# P09_DDRA_B_NOVTT.net
KiCad netlist of a schematic drawn in Altium Designer
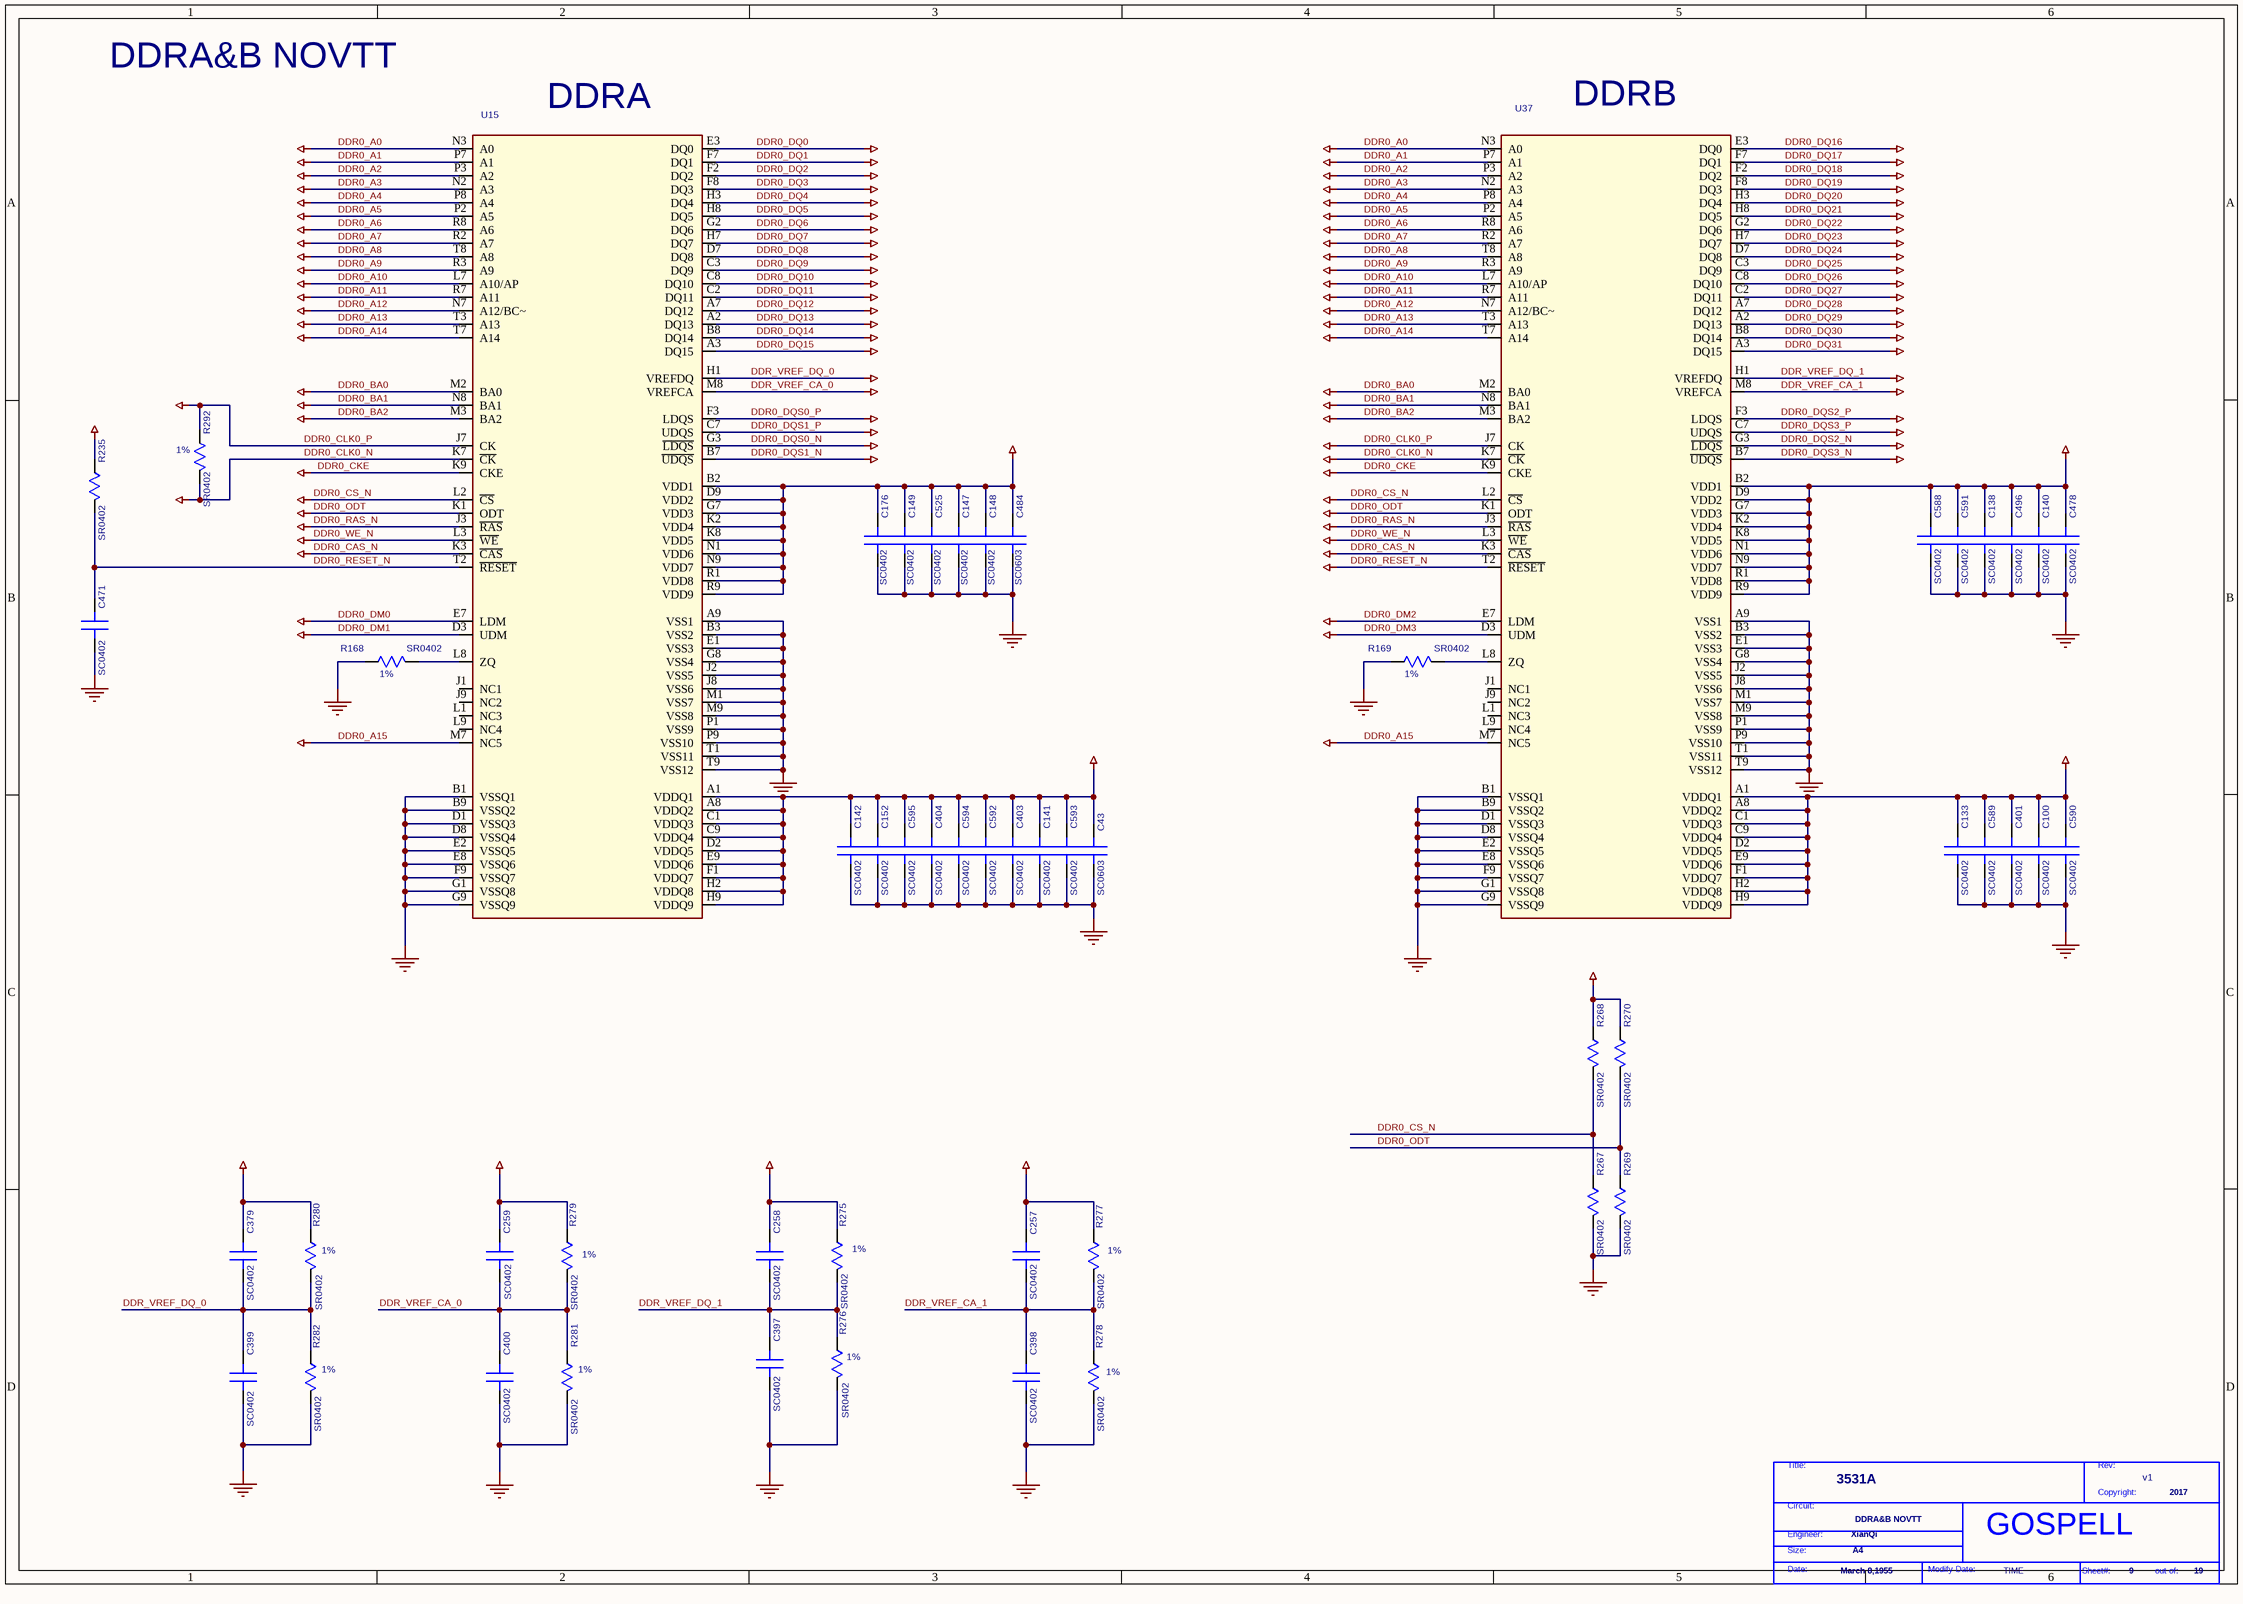
[diagram p0: P09 DDRA&B NOVTT.SchDoc]

(export (version "E")
  (design (tool "Eeschema 10.0.6"))
  (components
    (comp (ref "C43") (value "SC0603") (libsource (lib "*") (part "C_0_Dup2")))
    (comp (ref "C100") (value "SC0402") (libsource (lib "*") (part "C_0_Dup2")))
    (comp (ref "C133") (value "SC0402") (libsource (lib "*") (part "C_0_Dup2")))
    (comp (ref "C138") (value "SC0402") (libsource (lib "*") (part "C_0_Dup2")))
    (comp (ref "C140") (value "SC0402") (libsource (lib "*") (part "C_0_Dup2")))
    (comp (ref "C141") (value "SC0402") (libsource (lib "*") (part "C_0_Dup2")))
    (comp (ref "C142") (value "SC0402") (libsource (lib "*") (part "C_0_Dup2")))
    (comp (ref "C147") (value "SC0402") (libsource (lib "*") (part "C_0_Dup2")))
    (comp (ref "C148") (value "SC0402") (libsource (lib "*") (part "C_0_Dup2")))
    (comp (ref "C149") (value "SC0402") (libsource (lib "*") (part "C_0_Dup2")))
    (comp (ref "C152") (value "SC0402") (libsource (lib "*") (part "C_0_Dup2")))
    (comp (ref "C176") (value "SC0402") (libsource (lib "*") (part "C_0_Dup2")))
    (comp (ref "C257") (value "SC0402") (libsource (lib "*") (part "C_0_Dup2")))
    (comp (ref "C258") (value "SC0402") (libsource (lib "*") (part "C_0_Dup2")))
    (comp (ref "C259") (value "SC0402") (libsource (lib "*") (part "C_0_Dup2")))
    (comp (ref "C379") (value "SC0402") (libsource (lib "*") (part "C_0_Dup2")))
    (comp (ref "C397") (value "SC0402") (libsource (lib "*") (part "C_0_Dup2")))
    (comp (ref "C398") (value "SC0402") (libsource (lib "*") (part "C_0_Dup2")))
    (comp (ref "C399") (value "SC0402") (libsource (lib "*") (part "C_0_Dup2")))
    (comp (ref "C400") (value "SC0402") (libsource (lib "*") (part "C_0_Dup2")))
    (comp (ref "C401") (value "SC0402") (libsource (lib "*") (part "C_0_Dup2")))
    (comp (ref "C403") (value "SC0402") (libsource (lib "*") (part "C_0_Dup2")))
    (comp (ref "C404") (value "SC0402") (libsource (lib "*") (part "C_0_Dup2")))
    (comp (ref "C471") (value "SC0402") (libsource (lib "*") (part "C_0_Dup2")))
    (comp (ref "C478") (value "SC0402") (libsource (lib "*") (part "C_0_Dup2")))
    (comp (ref "C484") (value "SC0603") (libsource (lib "*") (part "C_0_Dup2")))
    (comp (ref "C496") (value "SC0402") (libsource (lib "*") (part "C_0_Dup2")))
    (comp (ref "C525") (value "SC0402") (libsource (lib "*") (part "C_0_Dup2")))
    (comp (ref "C588") (value "SC0402") (libsource (lib "*") (part "C_0_Dup2")))
    (comp (ref "C589") (value "SC0402") (libsource (lib "*") (part "C_0_Dup2")))
    (comp (ref "C590") (value "SC0402") (libsource (lib "*") (part "C_0_Dup2")))
    (comp (ref "C591") (value "SC0402") (libsource (lib "*") (part "C_0_Dup2")))
    (comp (ref "C592") (value "SC0402") (libsource (lib "*") (part "C_0_Dup2")))
    (comp (ref "C593") (value "SC0402") (libsource (lib "*") (part "C_0_Dup2")))
    (comp (ref "C594") (value "SC0402") (libsource (lib "*") (part "C_0_Dup2")))
    (comp (ref "C595") (value "SC0402") (libsource (lib "*") (part "C_0_Dup2")))
    (comp (ref "R168") (value "SR0402") (libsource (lib "*") (part "R_1")))
    (comp (ref "R169") (value "SR0402") (libsource (lib "*") (part "R_1")))
    (comp (ref "R235") (value "SR0402") (libsource (lib "*") (part "R_1")))
    (comp (ref "R267") (value "SR0402") (libsource (lib "*") (part "R_1")))
    (comp (ref "R268") (value "SR0402") (libsource (lib "*") (part "R_1")))
    (comp (ref "R269") (value "SR0402") (libsource (lib "*") (part "R_1")))
    (comp (ref "R270") (value "SR0402") (libsource (lib "*") (part "R_1")))
    (comp (ref "R275") (value "SR0402") (libsource (lib "*") (part "R_1")))
    (comp (ref "R276") (value "SR0402") (libsource (lib "*") (part "R_1")))
    (comp (ref "R277") (value "SR0402") (libsource (lib "*") (part "R_1")))
    (comp (ref "R278") (value "SR0402") (libsource (lib "*") (part "R_1")))
    (comp (ref "R279") (value "SR0402") (libsource (lib "*") (part "R_1")))
    (comp (ref "R280") (value "SR0402") (libsource (lib "*") (part "R_1")))
    (comp (ref "R281") (value "SR0402") (libsource (lib "*") (part "R_1")))
    (comp (ref "R282") (value "SR0402") (libsource (lib "*") (part "R_1")))
    (comp (ref "R292") (value "SR0402") (libsource (lib "*") (part "R_1")))
    (comp (ref "U15") (value "BGA96-32-1609M") (libsource (lib "*") (part "MT41J256M16RE-15E-D_2")))
    (comp (ref "U37") (value "BGA96-32-1609M") (libsource (lib "*") (part "MT41J256M16RE-15E-D_2")))
  )
  (nets
    (net (code "1") (name "1V5") (class "Default")
      (node (ref "C100") (pin "1") (pinfunction "A_1") (pintype "passive"))
      (node (ref "C133") (pin "1") (pinfunction "A_1") (pintype "passive"))
      (node (ref "C138") (pin "1") (pinfunction "A_1") (pintype "passive"))
      (node (ref "C140") (pin "1") (pinfunction "A_1") (pintype "passive"))
      (node (ref "C141") (pin "1") (pinfunction "A_1") (pintype "passive"))
      (node (ref "C142") (pin "1") (pinfunction "A_1") (pintype "passive"))
      (node (ref "C147") (pin "1") (pinfunction "A_1") (pintype "passive"))
      (node (ref "C148") (pin "1") (pinfunction "A_1") (pintype "passive"))
      (node (ref "C149") (pin "1") (pinfunction "A_1") (pintype "passive"))
      (node (ref "C152") (pin "1") (pinfunction "A_1") (pintype "passive"))
      (node (ref "C176") (pin "1") (pinfunction "A_1") (pintype "passive"))
      (node (ref "C257") (pin "1") (pinfunction "A_1") (pintype "passive"))
      (node (ref "C258") (pin "1") (pinfunction "A_1") (pintype "passive"))
      (node (ref "C259") (pin "1") (pinfunction "A_1") (pintype "passive"))
      (node (ref "C379") (pin "1") (pinfunction "A_1") (pintype "passive"))
      (node (ref "C401") (pin "1") (pinfunction "A_1") (pintype "passive"))
      (node (ref "C403") (pin "1") (pinfunction "A_1") (pintype "passive"))
      (node (ref "C404") (pin "1") (pinfunction "A_1") (pintype "passive"))
      (node (ref "C43") (pin "1") (pinfunction "A_1") (pintype "passive"))
      (node (ref "C478") (pin "1") (pinfunction "A_1") (pintype "passive"))
      (node (ref "C484") (pin "1") (pinfunction "A_1") (pintype "passive"))
      (node (ref "C496") (pin "1") (pinfunction "A_1") (pintype "passive"))
      (node (ref "C525") (pin "1") (pinfunction "A_1") (pintype "passive"))
      (node (ref "C588") (pin "1") (pinfunction "A_1") (pintype "passive"))
      (node (ref "C589") (pin "1") (pinfunction "A_1") (pintype "passive"))
      (node (ref "C590") (pin "1") (pinfunction "A_1") (pintype "passive"))
      (node (ref "C591") (pin "1") (pinfunction "A_1") (pintype "passive"))
      (node (ref "C592") (pin "1") (pinfunction "A_1") (pintype "passive"))
      (node (ref "C593") (pin "1") (pinfunction "A_1") (pintype "passive"))
      (node (ref "C594") (pin "1") (pinfunction "A_1") (pintype "passive"))
      (node (ref "C595") (pin "1") (pinfunction "A_1") (pintype "passive"))
      (node (ref "R235") (pin "1") (pinfunction "A_1") (pintype "passive"))
      (node (ref "R268") (pin "1") (pinfunction "A_1") (pintype "passive"))
      (node (ref "R270") (pin "1") (pinfunction "A_1") (pintype "passive"))
      (node (ref "R275") (pin "1") (pinfunction "A_1") (pintype "passive"))
      (node (ref "R277") (pin "1") (pinfunction "A_1") (pintype "passive"))
      (node (ref "R279") (pin "1") (pinfunction "A_1") (pintype "passive"))
      (node (ref "R280") (pin "1") (pinfunction "A_1") (pintype "passive"))
      (node (ref "U15") (pin "A1") (pinfunction "VDDQ1_A1") (pintype "passive"))
      (node (ref "U15") (pin "A8") (pinfunction "VDDQ2_A8") (pintype "passive"))
      (node (ref "U15") (pin "B2") (pinfunction "VDD1_B2") (pintype "passive"))
      (node (ref "U15") (pin "C1") (pinfunction "VDDQ3_C1") (pintype "passive"))
      (node (ref "U15") (pin "C9") (pinfunction "VDDQ4_C9") (pintype "passive"))
      (node (ref "U15") (pin "D2") (pinfunction "VDDQ5_D2") (pintype "passive"))
      (node (ref "U15") (pin "D9") (pinfunction "VDD2_D9") (pintype "passive"))
      (node (ref "U15") (pin "E9") (pinfunction "VDDQ6_E9") (pintype "passive"))
      (node (ref "U15") (pin "F1") (pinfunction "VDDQ7_F1") (pintype "passive"))
      (node (ref "U15") (pin "G7") (pinfunction "VDD3_G7") (pintype "passive"))
      (node (ref "U15") (pin "H2") (pinfunction "VDDQ8_H2") (pintype "passive"))
      (node (ref "U15") (pin "H9") (pinfunction "VDDQ9_H9") (pintype "passive"))
      (node (ref "U15") (pin "K2") (pinfunction "VDD4_K2") (pintype "passive"))
      (node (ref "U15") (pin "K8") (pinfunction "VDD5_K8") (pintype "passive"))
      (node (ref "U15") (pin "N1") (pinfunction "VDD6_N1") (pintype "passive"))
      (node (ref "U15") (pin "N9") (pinfunction "VDD7_N9") (pintype "passive"))
      (node (ref "U15") (pin "R1") (pinfunction "VDD8_R1") (pintype "passive"))
      (node (ref "U15") (pin "R9") (pinfunction "VDD9_R9") (pintype "passive"))
      (node (ref "U37") (pin "A1") (pinfunction "VDDQ1_A1") (pintype "passive"))
      (node (ref "U37") (pin "A8") (pinfunction "VDDQ2_A8") (pintype "passive"))
      (node (ref "U37") (pin "B2") (pinfunction "VDD1_B2") (pintype "passive"))
      (node (ref "U37") (pin "C1") (pinfunction "VDDQ3_C1") (pintype "passive"))
      (node (ref "U37") (pin "C9") (pinfunction "VDDQ4_C9") (pintype "passive"))
      (node (ref "U37") (pin "D2") (pinfunction "VDDQ5_D2") (pintype "passive"))
      (node (ref "U37") (pin "D9") (pinfunction "VDD2_D9") (pintype "passive"))
      (node (ref "U37") (pin "E9") (pinfunction "VDDQ6_E9") (pintype "passive"))
      (node (ref "U37") (pin "F1") (pinfunction "VDDQ7_F1") (pintype "passive"))
      (node (ref "U37") (pin "G7") (pinfunction "VDD3_G7") (pintype "passive"))
      (node (ref "U37") (pin "H2") (pinfunction "VDDQ8_H2") (pintype "passive"))
      (node (ref "U37") (pin "H9") (pinfunction "VDDQ9_H9") (pintype "passive"))
      (node (ref "U37") (pin "K2") (pinfunction "VDD4_K2") (pintype "passive"))
      (node (ref "U37") (pin "K8") (pinfunction "VDD5_K8") (pintype "passive"))
      (node (ref "U37") (pin "N1") (pinfunction "VDD6_N1") (pintype "passive"))
      (node (ref "U37") (pin "N9") (pinfunction "VDD7_N9") (pintype "passive"))
      (node (ref "U37") (pin "R1") (pinfunction "VDD8_R1") (pintype "passive"))
      (node (ref "U37") (pin "R9") (pinfunction "VDD9_R9") (pintype "passive"))
    )
    (net (code "2") (name "DDR0_A0") (class "Default")
      (node (ref "U15") (pin "N3") (pinfunction "A0_N3") (pintype "passive"))
      (node (ref "U37") (pin "N3") (pinfunction "A0_N3") (pintype "passive"))
    )
    (net (code "3") (name "DDR0_A1") (class "Default")
      (node (ref "U15") (pin "P7") (pinfunction "A1_P7") (pintype "passive"))
      (node (ref "U37") (pin "P7") (pinfunction "A1_P7") (pintype "passive"))
    )
    (net (code "4") (name "DDR0_A2") (class "Default")
      (node (ref "U15") (pin "P3") (pinfunction "A2_P3") (pintype "passive"))
      (node (ref "U37") (pin "P3") (pinfunction "A2_P3") (pintype "passive"))
    )
    (net (code "5") (name "DDR0_A3") (class "Default")
      (node (ref "U15") (pin "N2") (pinfunction "A3_N2") (pintype "passive"))
      (node (ref "U37") (pin "N2") (pinfunction "A3_N2") (pintype "passive"))
    )
    (net (code "6") (name "DDR0_A4") (class "Default")
      (node (ref "U15") (pin "P8") (pinfunction "A4_P8") (pintype "passive"))
      (node (ref "U37") (pin "P8") (pinfunction "A4_P8") (pintype "passive"))
    )
    (net (code "7") (name "DDR0_A5") (class "Default")
      (node (ref "U15") (pin "P2") (pinfunction "A5_P2") (pintype "passive"))
      (node (ref "U37") (pin "P2") (pinfunction "A5_P2") (pintype "passive"))
    )
    (net (code "8") (name "DDR0_A6") (class "Default")
      (node (ref "U15") (pin "R8") (pinfunction "A6_R8") (pintype "passive"))
      (node (ref "U37") (pin "R8") (pinfunction "A6_R8") (pintype "passive"))
    )
    (net (code "9") (name "DDR0_A7") (class "Default")
      (node (ref "U15") (pin "R2") (pinfunction "A7_R2") (pintype "passive"))
      (node (ref "U37") (pin "R2") (pinfunction "A7_R2") (pintype "passive"))
    )
    (net (code "10") (name "DDR0_A8") (class "Default")
      (node (ref "U15") (pin "T8") (pinfunction "A8_T8") (pintype "passive"))
      (node (ref "U37") (pin "T8") (pinfunction "A8_T8") (pintype "passive"))
    )
    (net (code "11") (name "DDR0_A9") (class "Default")
      (node (ref "U15") (pin "R3") (pinfunction "A9_R3") (pintype "passive"))
      (node (ref "U37") (pin "R3") (pinfunction "A9_R3") (pintype "passive"))
    )
    (net (code "12") (name "DDR0_A10") (class "Default")
      (node (ref "U15") (pin "L7") (pinfunction "A10/AP_L7") (pintype "passive"))
      (node (ref "U37") (pin "L7") (pinfunction "A10/AP_L7") (pintype "passive"))
    )
    (net (code "13") (name "DDR0_A11") (class "Default")
      (node (ref "U15") (pin "R7") (pinfunction "A11_R7") (pintype "passive"))
      (node (ref "U37") (pin "R7") (pinfunction "A11_R7") (pintype "passive"))
    )
    (net (code "14") (name "DDR0_A12") (class "Default")
      (node (ref "U15") (pin "N7") (pinfunction "A12/BC~_N7") (pintype "passive"))
      (node (ref "U37") (pin "N7") (pinfunction "A12/BC~_N7") (pintype "passive"))
    )
    (net (code "15") (name "DDR0_A13") (class "Default")
      (node (ref "U15") (pin "T3") (pinfunction "A13_T3") (pintype "passive"))
      (node (ref "U37") (pin "T3") (pinfunction "A13_T3") (pintype "passive"))
    )
    (net (code "16") (name "DDR0_A14") (class "Default")
      (node (ref "U15") (pin "T7") (pinfunction "A14_T7") (pintype "passive"))
      (node (ref "U37") (pin "T7") (pinfunction "A14_T7") (pintype "passive"))
    )
    (net (code "17") (name "DDR0_A15") (class "Default")
      (node (ref "U15") (pin "M7") (pinfunction "NC5_M7") (pintype "passive"))
      (node (ref "U37") (pin "M7") (pinfunction "NC5_M7") (pintype "passive"))
    )
    (net (code "18") (name "DDR0_BA0") (class "Default")
      (node (ref "U15") (pin "M2") (pinfunction "BA0_M2") (pintype "passive"))
      (node (ref "U37") (pin "M2") (pinfunction "BA0_M2") (pintype "passive"))
    )
    (net (code "19") (name "DDR0_BA1") (class "Default")
      (node (ref "U15") (pin "N8") (pinfunction "BA1_N8") (pintype "passive"))
      (node (ref "U37") (pin "N8") (pinfunction "BA1_N8") (pintype "passive"))
    )
    (net (code "20") (name "DDR0_BA2") (class "Default")
      (node (ref "U15") (pin "M3") (pinfunction "BA2_M3") (pintype "passive"))
      (node (ref "U37") (pin "M3") (pinfunction "BA2_M3") (pintype "passive"))
    )
    (net (code "21") (name "DDR0_CAS_N") (class "Default")
      (node (ref "U15") (pin "K3") (pinfunction "~{CAS}_K3") (pintype "passive"))
      (node (ref "U37") (pin "K3") (pinfunction "~{CAS}_K3") (pintype "passive"))
    )
    (net (code "22") (name "DDR0_CKE") (class "Default")
      (node (ref "U15") (pin "K9") (pinfunction "CKE_K9") (pintype "passive"))
      (node (ref "U37") (pin "K9") (pinfunction "CKE_K9") (pintype "passive"))
    )
    (net (code "23") (name "DDR0_CLK0_N") (class "Default")
      (node (ref "R292") (pin "2") (pinfunction "B_2") (pintype "passive"))
      (node (ref "U15") (pin "K7") (pinfunction "~{CK}_K7") (pintype "passive"))
      (node (ref "U37") (pin "K7") (pinfunction "~{CK}_K7") (pintype "passive"))
    )
    (net (code "24") (name "DDR0_CLK0_P") (class "Default")
      (node (ref "R292") (pin "1") (pinfunction "A_1") (pintype "passive"))
      (node (ref "U15") (pin "J7") (pinfunction "CK_J7") (pintype "passive"))
      (node (ref "U37") (pin "J7") (pinfunction "CK_J7") (pintype "passive"))
    )
    (net (code "25") (name "DDR0_CS_N") (class "Default")
      (node (ref "R267") (pin "1") (pinfunction "A_1") (pintype "passive"))
      (node (ref "R268") (pin "2") (pinfunction "B_2") (pintype "passive"))
      (node (ref "U15") (pin "L2") (pinfunction "~{CS}_L2") (pintype "passive"))
      (node (ref "U37") (pin "L2") (pinfunction "~{CS}_L2") (pintype "passive"))
    )
    (net (code "26") (name "DDR0_DM0") (class "Default")
      (node (ref "U15") (pin "E7") (pinfunction "LDM_E7") (pintype "passive"))
    )
    (net (code "27") (name "DDR0_DM1") (class "Default")
      (node (ref "U15") (pin "D3") (pinfunction "UDM_D3") (pintype "passive"))
    )
    (net (code "28") (name "DDR0_DM2") (class "Default")
      (node (ref "U37") (pin "E7") (pinfunction "LDM_E7") (pintype "passive"))
    )
    (net (code "29") (name "DDR0_DM3") (class "Default")
      (node (ref "U37") (pin "D3") (pinfunction "UDM_D3") (pintype "passive"))
    )
    (net (code "30") (name "DDR0_DQ0") (class "Default")
      (node (ref "U15") (pin "E3") (pinfunction "DQ0_E3") (pintype "passive"))
    )
    (net (code "31") (name "DDR0_DQ1") (class "Default")
      (node (ref "U15") (pin "F7") (pinfunction "DQ1_F7") (pintype "passive"))
    )
    (net (code "32") (name "DDR0_DQ2") (class "Default")
      (node (ref "U15") (pin "F2") (pinfunction "DQ2_F2") (pintype "passive"))
    )
    (net (code "33") (name "DDR0_DQ3") (class "Default")
      (node (ref "U15") (pin "F8") (pinfunction "DQ3_F8") (pintype "passive"))
    )
    (net (code "34") (name "DDR0_DQ4") (class "Default")
      (node (ref "U15") (pin "H3") (pinfunction "DQ4_H3") (pintype "passive"))
    )
    (net (code "35") (name "DDR0_DQ5") (class "Default")
      (node (ref "U15") (pin "H8") (pinfunction "DQ5_H8") (pintype "passive"))
    )
    (net (code "36") (name "DDR0_DQ6") (class "Default")
      (node (ref "U15") (pin "G2") (pinfunction "DQ6_G2") (pintype "passive"))
    )
    (net (code "37") (name "DDR0_DQ7") (class "Default")
      (node (ref "U15") (pin "H7") (pinfunction "DQ7_H7") (pintype "passive"))
    )
    (net (code "38") (name "DDR0_DQ8") (class "Default")
      (node (ref "U15") (pin "D7") (pinfunction "DQ8_D7") (pintype "passive"))
    )
    (net (code "39") (name "DDR0_DQ9") (class "Default")
      (node (ref "U15") (pin "C3") (pinfunction "DQ9_C3") (pintype "passive"))
    )
    (net (code "40") (name "DDR0_DQ10") (class "Default")
      (node (ref "U15") (pin "C8") (pinfunction "DQ10_C8") (pintype "passive"))
    )
    (net (code "41") (name "DDR0_DQ11") (class "Default")
      (node (ref "U15") (pin "C2") (pinfunction "DQ11_C2") (pintype "passive"))
    )
    (net (code "42") (name "DDR0_DQ12") (class "Default")
      (node (ref "U15") (pin "A7") (pinfunction "DQ12_A7") (pintype "passive"))
    )
    (net (code "43") (name "DDR0_DQ13") (class "Default")
      (node (ref "U15") (pin "A2") (pinfunction "DQ13_A2") (pintype "passive"))
    )
    (net (code "44") (name "DDR0_DQ14") (class "Default")
      (node (ref "U15") (pin "B8") (pinfunction "DQ14_B8") (pintype "passive"))
    )
    (net (code "45") (name "DDR0_DQ15") (class "Default")
      (node (ref "U15") (pin "A3") (pinfunction "DQ15_A3") (pintype "passive"))
    )
    (net (code "46") (name "DDR0_DQ16") (class "Default")
      (node (ref "U37") (pin "E3") (pinfunction "DQ0_E3") (pintype "passive"))
    )
    (net (code "47") (name "DDR0_DQ17") (class "Default")
      (node (ref "U37") (pin "F7") (pinfunction "DQ1_F7") (pintype "passive"))
    )
    (net (code "48") (name "DDR0_DQ18") (class "Default")
      (node (ref "U37") (pin "F2") (pinfunction "DQ2_F2") (pintype "passive"))
    )
    (net (code "49") (name "DDR0_DQ19") (class "Default")
      (node (ref "U37") (pin "F8") (pinfunction "DQ3_F8") (pintype "passive"))
    )
    (net (code "50") (name "DDR0_DQ20") (class "Default")
      (node (ref "U37") (pin "H3") (pinfunction "DQ4_H3") (pintype "passive"))
    )
    (net (code "51") (name "DDR0_DQ21") (class "Default")
      (node (ref "U37") (pin "H8") (pinfunction "DQ5_H8") (pintype "passive"))
    )
    (net (code "52") (name "DDR0_DQ22") (class "Default")
      (node (ref "U37") (pin "G2") (pinfunction "DQ6_G2") (pintype "passive"))
    )
    (net (code "53") (name "DDR0_DQ23") (class "Default")
      (node (ref "U37") (pin "H7") (pinfunction "DQ7_H7") (pintype "passive"))
    )
    (net (code "54") (name "DDR0_DQ24") (class "Default")
      (node (ref "U37") (pin "D7") (pinfunction "DQ8_D7") (pintype "passive"))
    )
    (net (code "55") (name "DDR0_DQ25") (class "Default")
      (node (ref "U37") (pin "C3") (pinfunction "DQ9_C3") (pintype "passive"))
    )
    (net (code "56") (name "DDR0_DQ26") (class "Default")
      (node (ref "U37") (pin "C8") (pinfunction "DQ10_C8") (pintype "passive"))
    )
    (net (code "57") (name "DDR0_DQ27") (class "Default")
      (node (ref "U37") (pin "C2") (pinfunction "DQ11_C2") (pintype "passive"))
    )
    (net (code "58") (name "DDR0_DQ28") (class "Default")
      (node (ref "U37") (pin "A7") (pinfunction "DQ12_A7") (pintype "passive"))
    )
    (net (code "59") (name "DDR0_DQ29") (class "Default")
      (node (ref "U37") (pin "A2") (pinfunction "DQ13_A2") (pintype "passive"))
    )
    (net (code "60") (name "DDR0_DQ30") (class "Default")
      (node (ref "U37") (pin "B8") (pinfunction "DQ14_B8") (pintype "passive"))
    )
    (net (code "61") (name "DDR0_DQ31") (class "Default")
      (node (ref "U37") (pin "A3") (pinfunction "DQ15_A3") (pintype "passive"))
    )
    (net (code "62") (name "DDR0_DQS0_N") (class "Default")
      (node (ref "U15") (pin "G3") (pinfunction "~{LDQS}_G3") (pintype "passive"))
    )
    (net (code "63") (name "DDR0_DQS0_P") (class "Default")
      (node (ref "U15") (pin "F3") (pinfunction "LDQS_F3") (pintype "passive"))
    )
    (net (code "64") (name "DDR0_DQS1_N") (class "Default")
      (node (ref "U15") (pin "B7") (pinfunction "~{UDQS}_B7") (pintype "passive"))
    )
    (net (code "65") (name "DDR0_DQS1_P") (class "Default")
      (node (ref "U15") (pin "C7") (pinfunction "UDQS_C7") (pintype "passive"))
    )
    (net (code "66") (name "DDR0_DQS2_N") (class "Default")
      (node (ref "U37") (pin "G3") (pinfunction "~{LDQS}_G3") (pintype "passive"))
    )
    (net (code "67") (name "DDR0_DQS2_P") (class "Default")
      (node (ref "U37") (pin "F3") (pinfunction "LDQS_F3") (pintype "passive"))
    )
    (net (code "68") (name "DDR0_DQS3_N") (class "Default")
      (node (ref "U37") (pin "B7") (pinfunction "~{UDQS}_B7") (pintype "passive"))
    )
    (net (code "69") (name "DDR0_DQS3_P") (class "Default")
      (node (ref "U37") (pin "C7") (pinfunction "UDQS_C7") (pintype "passive"))
    )
    (net (code "70") (name "DDR0_ODT") (class "Default")
      (node (ref "R269") (pin "1") (pinfunction "A_1") (pintype "passive"))
      (node (ref "R270") (pin "2") (pinfunction "B_2") (pintype "passive"))
      (node (ref "U15") (pin "K1") (pinfunction "ODT_K1") (pintype "passive"))
      (node (ref "U37") (pin "K1") (pinfunction "ODT_K1") (pintype "passive"))
    )
    (net (code "71") (name "DDR0_RAS_N") (class "Default")
      (node (ref "U15") (pin "J3") (pinfunction "~{RAS}_J3") (pintype "passive"))
      (node (ref "U37") (pin "J3") (pinfunction "~{RAS}_J3") (pintype "passive"))
    )
    (net (code "72") (name "DDR0_RESET_N") (class "Default")
      (node (ref "C471") (pin "1") (pinfunction "A_1") (pintype "passive"))
      (node (ref "R235") (pin "2") (pinfunction "B_2") (pintype "passive"))
      (node (ref "U15") (pin "T2") (pinfunction "~{RESET}_T2") (pintype "passive"))
      (node (ref "U37") (pin "T2") (pinfunction "~{RESET}_T2") (pintype "passive"))
    )
    (net (code "73") (name "DDR0_WE_N") (class "Default")
      (node (ref "U15") (pin "L3") (pinfunction "~{WE}_L3") (pintype "passive"))
      (node (ref "U37") (pin "L3") (pinfunction "~{WE}_L3") (pintype "passive"))
    )
    (net (code "74") (name "DDR_VREF_CA_0") (class "Default")
      (node (ref "C259") (pin "2") (pinfunction "B_2") (pintype "passive"))
      (node (ref "C400") (pin "1") (pinfunction "A_1") (pintype "passive"))
      (node (ref "R279") (pin "2") (pinfunction "B_2") (pintype "passive"))
      (node (ref "R281") (pin "1") (pinfunction "A_1") (pintype "passive"))
      (node (ref "U15") (pin "M8") (pinfunction "VREFCA_M8") (pintype "passive"))
    )
    (net (code "75") (name "DDR_VREF_CA_1") (class "Default")
      (node (ref "C257") (pin "2") (pinfunction "B_2") (pintype "passive"))
      (node (ref "C398") (pin "1") (pinfunction "A_1") (pintype "passive"))
      (node (ref "R277") (pin "2") (pinfunction "B_2") (pintype "passive"))
      (node (ref "R278") (pin "1") (pinfunction "A_1") (pintype "passive"))
      (node (ref "U37") (pin "M8") (pinfunction "VREFCA_M8") (pintype "passive"))
    )
    (net (code "76") (name "DDR_VREF_DQ_0") (class "Default")
      (node (ref "C379") (pin "2") (pinfunction "B_2") (pintype "passive"))
      (node (ref "C399") (pin "1") (pinfunction "A_1") (pintype "passive"))
      (node (ref "R280") (pin "2") (pinfunction "B_2") (pintype "passive"))
      (node (ref "R282") (pin "1") (pinfunction "A_1") (pintype "passive"))
      (node (ref "U15") (pin "H1") (pinfunction "VREFDQ_H1") (pintype "passive"))
    )
    (net (code "77") (name "DDR_VREF_DQ_1") (class "Default")
      (node (ref "C258") (pin "2") (pinfunction "B_2") (pintype "passive"))
      (node (ref "C397") (pin "1") (pinfunction "A_1") (pintype "passive"))
      (node (ref "R275") (pin "2") (pinfunction "B_2") (pintype "passive"))
      (node (ref "R276") (pin "1") (pinfunction "A_1") (pintype "passive"))
      (node (ref "U37") (pin "H1") (pinfunction "VREFDQ_H1") (pintype "passive"))
    )
    (net (code "78") (name "GND") (class "Default")
      (node (ref "C100") (pin "2") (pinfunction "B_2") (pintype "passive"))
      (node (ref "C133") (pin "2") (pinfunction "B_2") (pintype "passive"))
      (node (ref "C138") (pin "2") (pinfunction "B_2") (pintype "passive"))
      (node (ref "C140") (pin "2") (pinfunction "B_2") (pintype "passive"))
      (node (ref "C141") (pin "2") (pinfunction "B_2") (pintype "passive"))
      (node (ref "C142") (pin "2") (pinfunction "B_2") (pintype "passive"))
      (node (ref "C147") (pin "2") (pinfunction "B_2") (pintype "passive"))
      (node (ref "C148") (pin "2") (pinfunction "B_2") (pintype "passive"))
      (node (ref "C149") (pin "2") (pinfunction "B_2") (pintype "passive"))
      (node (ref "C152") (pin "2") (pinfunction "B_2") (pintype "passive"))
      (node (ref "C176") (pin "2") (pinfunction "B_2") (pintype "passive"))
      (node (ref "C397") (pin "2") (pinfunction "B_2") (pintype "passive"))
      (node (ref "C398") (pin "2") (pinfunction "B_2") (pintype "passive"))
      (node (ref "C399") (pin "2") (pinfunction "B_2") (pintype "passive"))
      (node (ref "C400") (pin "2") (pinfunction "B_2") (pintype "passive"))
      (node (ref "C401") (pin "2") (pinfunction "B_2") (pintype "passive"))
      (node (ref "C403") (pin "2") (pinfunction "B_2") (pintype "passive"))
      (node (ref "C404") (pin "2") (pinfunction "B_2") (pintype "passive"))
      (node (ref "C43") (pin "2") (pinfunction "B_2") (pintype "passive"))
      (node (ref "C471") (pin "2") (pinfunction "B_2") (pintype "passive"))
      (node (ref "C478") (pin "2") (pinfunction "B_2") (pintype "passive"))
      (node (ref "C484") (pin "2") (pinfunction "B_2") (pintype "passive"))
      (node (ref "C496") (pin "2") (pinfunction "B_2") (pintype "passive"))
      (node (ref "C525") (pin "2") (pinfunction "B_2") (pintype "passive"))
      (node (ref "C588") (pin "2") (pinfunction "B_2") (pintype "passive"))
      (node (ref "C589") (pin "2") (pinfunction "B_2") (pintype "passive"))
      (node (ref "C590") (pin "2") (pinfunction "B_2") (pintype "passive"))
      (node (ref "C591") (pin "2") (pinfunction "B_2") (pintype "passive"))
      (node (ref "C592") (pin "2") (pinfunction "B_2") (pintype "passive"))
      (node (ref "C593") (pin "2") (pinfunction "B_2") (pintype "passive"))
      (node (ref "C594") (pin "2") (pinfunction "B_2") (pintype "passive"))
      (node (ref "C595") (pin "2") (pinfunction "B_2") (pintype "passive"))
      (node (ref "R168") (pin "1") (pinfunction "A_1") (pintype "passive"))
      (node (ref "R169") (pin "1") (pinfunction "A_1") (pintype "passive"))
      (node (ref "R267") (pin "2") (pinfunction "B_2") (pintype "passive"))
      (node (ref "R269") (pin "2") (pinfunction "B_2") (pintype "passive"))
      (node (ref "R276") (pin "2") (pinfunction "B_2") (pintype "passive"))
      (node (ref "R278") (pin "2") (pinfunction "B_2") (pintype "passive"))
      (node (ref "R281") (pin "2") (pinfunction "B_2") (pintype "passive"))
      (node (ref "R282") (pin "2") (pinfunction "B_2") (pintype "passive"))
      (node (ref "U15") (pin "A9") (pinfunction "VSS1_A9") (pintype "passive"))
      (node (ref "U15") (pin "B1") (pinfunction "VSSQ1_B1") (pintype "passive"))
      (node (ref "U15") (pin "B3") (pinfunction "VSS2_B3") (pintype "passive"))
      (node (ref "U15") (pin "B9") (pinfunction "VSSQ2_B9") (pintype "passive"))
      (node (ref "U15") (pin "D1") (pinfunction "VSSQ3_D1") (pintype "passive"))
      (node (ref "U15") (pin "D8") (pinfunction "VSSQ4_D8") (pintype "passive"))
      (node (ref "U15") (pin "E1") (pinfunction "VSS3_E1") (pintype "passive"))
      (node (ref "U15") (pin "E2") (pinfunction "VSSQ5_E2") (pintype "passive"))
      (node (ref "U15") (pin "E8") (pinfunction "VSSQ6_E8") (pintype "passive"))
      (node (ref "U15") (pin "F9") (pinfunction "VSSQ7_F9") (pintype "passive"))
      (node (ref "U15") (pin "G1") (pinfunction "VSSQ8_G1") (pintype "passive"))
      (node (ref "U15") (pin "G8") (pinfunction "VSS4_G8") (pintype "passive"))
      (node (ref "U15") (pin "G9") (pinfunction "VSSQ9_G9") (pintype "passive"))
      (node (ref "U15") (pin "J2") (pinfunction "VSS5_J2") (pintype "passive"))
      (node (ref "U15") (pin "J8") (pinfunction "VSS6_J8") (pintype "passive"))
      (node (ref "U15") (pin "M1") (pinfunction "VSS7_M1") (pintype "passive"))
      (node (ref "U15") (pin "M9") (pinfunction "VSS8_M9") (pintype "passive"))
      (node (ref "U15") (pin "P1") (pinfunction "VSS9_P1") (pintype "passive"))
      (node (ref "U15") (pin "P9") (pinfunction "VSS10_P9") (pintype "passive"))
      (node (ref "U15") (pin "T1") (pinfunction "VSS11_T1") (pintype "passive"))
      (node (ref "U15") (pin "T9") (pinfunction "VSS12_T9") (pintype "passive"))
      (node (ref "U37") (pin "A9") (pinfunction "VSS1_A9") (pintype "passive"))
      (node (ref "U37") (pin "B1") (pinfunction "VSSQ1_B1") (pintype "passive"))
      (node (ref "U37") (pin "B3") (pinfunction "VSS2_B3") (pintype "passive"))
      (node (ref "U37") (pin "B9") (pinfunction "VSSQ2_B9") (pintype "passive"))
      (node (ref "U37") (pin "D1") (pinfunction "VSSQ3_D1") (pintype "passive"))
      (node (ref "U37") (pin "D8") (pinfunction "VSSQ4_D8") (pintype "passive"))
      (node (ref "U37") (pin "E1") (pinfunction "VSS3_E1") (pintype "passive"))
      (node (ref "U37") (pin "E2") (pinfunction "VSSQ5_E2") (pintype "passive"))
      (node (ref "U37") (pin "E8") (pinfunction "VSSQ6_E8") (pintype "passive"))
      (node (ref "U37") (pin "F9") (pinfunction "VSSQ7_F9") (pintype "passive"))
      (node (ref "U37") (pin "G1") (pinfunction "VSSQ8_G1") (pintype "passive"))
      (node (ref "U37") (pin "G8") (pinfunction "VSS4_G8") (pintype "passive"))
      (node (ref "U37") (pin "G9") (pinfunction "VSSQ9_G9") (pintype "passive"))
      (node (ref "U37") (pin "J2") (pinfunction "VSS5_J2") (pintype "passive"))
      (node (ref "U37") (pin "J8") (pinfunction "VSS6_J8") (pintype "passive"))
      (node (ref "U37") (pin "M1") (pinfunction "VSS7_M1") (pintype "passive"))
      (node (ref "U37") (pin "M9") (pinfunction "VSS8_M9") (pintype "passive"))
      (node (ref "U37") (pin "P1") (pinfunction "VSS9_P1") (pintype "passive"))
      (node (ref "U37") (pin "P9") (pinfunction "VSS10_P9") (pintype "passive"))
      (node (ref "U37") (pin "T1") (pinfunction "VSS11_T1") (pintype "passive"))
      (node (ref "U37") (pin "T9") (pinfunction "VSS12_T9") (pintype "passive"))
    )
    (net (code "79") (name "Net-(R168-B)") (class "Default")
      (node (ref "R168") (pin "2") (pinfunction "B_2") (pintype "passive"))
      (node (ref "U15") (pin "L8") (pinfunction "ZQ_L8") (pintype "passive"))
    )
    (net (code "80") (name "Net-(R169-B)") (class "Default")
      (node (ref "R169") (pin "2") (pinfunction "B_2") (pintype "passive"))
      (node (ref "U37") (pin "L8") (pinfunction "ZQ_L8") (pintype "passive"))
    )
    (net (code "81") (name "unconnected-(U15-NC1-PadJ1)") (class "Default")
      (node (ref "U15") (pin "J1") (pinfunction "NC1_J1") (pintype "passive"))
    )
    (net (code "82") (name "unconnected-(U15-NC2-PadJ9)") (class "Default")
      (node (ref "U15") (pin "J9") (pinfunction "NC2_J9") (pintype "passive"))
    )
    (net (code "83") (name "unconnected-(U15-NC3-PadL1)") (class "Default")
      (node (ref "U15") (pin "L1") (pinfunction "NC3_L1") (pintype "passive"))
    )
    (net (code "84") (name "unconnected-(U15-NC4-PadL9)") (class "Default")
      (node (ref "U15") (pin "L9") (pinfunction "NC4_L9") (pintype "passive"))
    )
    (net (code "85") (name "unconnected-(U37-NC1-PadJ1)") (class "Default")
      (node (ref "U37") (pin "J1") (pinfunction "NC1_J1") (pintype "passive"))
    )
    (net (code "86") (name "unconnected-(U37-NC2-PadJ9)") (class "Default")
      (node (ref "U37") (pin "J9") (pinfunction "NC2_J9") (pintype "passive"))
    )
    (net (code "87") (name "unconnected-(U37-NC3-PadL1)") (class "Default")
      (node (ref "U37") (pin "L1") (pinfunction "NC3_L1") (pintype "passive"))
    )
    (net (code "88") (name "unconnected-(U37-NC4-PadL9)") (class "Default")
      (node (ref "U37") (pin "L9") (pinfunction "NC4_L9") (pintype "passive"))
    )
  )
)
